# ATtiny.net
KiCad netlist of a schematic drawn in Altium Designer
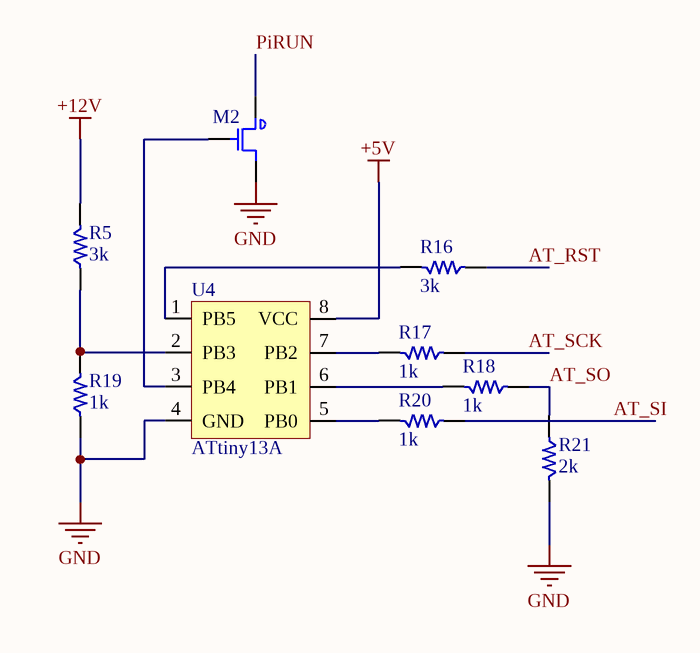
[diagram p0: ATtiny.SchDoc]

(export (version "E")
  (design (tool "Eeschema 10.0.6"))
  (components
    (comp (ref "M2")
      (value "N-CH Mosfet Switch")
      (footprint "SOT32-3")
      (description "MOSFET N-CH 20V 1.05A SOT23")
      (fields
        (field (name "MANUFACTURER") "NXP USA Inc.")
        (field (name "MANUFACTURER PART NUMBER") "BSH105,215")
      )
      (libsource (lib "SIM808") (part "BSH105,215"))
    )
    (comp (ref "R5")
      (value "3k")
      (footprint "0805")
      (description "Generic Resistor")
      (fields (field (name "Comment") "Resistor"))
      (libsource (lib "PowerCircuit") (part "Resistor"))
    )
    (comp (ref "R16")
      (value "3k")
      (footprint "0805")
      (description "Generic Resistor")
      (fields (field (name "Comment") "Resistor"))
      (libsource (lib "PowerCircuit") (part "Resistor"))
    )
    (comp (ref "R17")
      (value "1k")
      (footprint "0805")
      (description "Generic Resistor")
      (fields (field (name "Comment") "Resistor"))
      (libsource (lib "PowerCircuit") (part "Resistor"))
    )
    (comp (ref "R18")
      (value "1k")
      (footprint "0805")
      (description "Generic Resistor")
      (fields (field (name "Comment") "Resistor"))
      (libsource (lib "PowerCircuit") (part "Resistor"))
    )
    (comp (ref "R19")
      (value "1k")
      (footprint "0805")
      (description "Generic Resistor")
      (fields (field (name "Comment") "Resistor"))
      (libsource (lib "PowerCircuit") (part "Resistor"))
    )
    (comp (ref "R20")
      (value "1k")
      (footprint "0805")
      (description "Generic Resistor")
      (fields (field (name "Comment") "Resistor"))
      (libsource (lib "PowerCircuit") (part "Resistor"))
    )
    (comp (ref "R21")
      (value "2k")
      (footprint "0805")
      (description "Generic Resistor")
      (fields (field (name "Comment") "Resistor"))
      (libsource (lib "PowerCircuit") (part "Resistor"))
    )
    (comp (ref "U4")
      (value "ATtiny13A")
      (footprint "ATtiny13A")
      (fields
        (field (name "MANUFACTURER") "Microchip Technology")
        (field (name "MANUFACTURER PART NUMBER") "ATTINY13A-SSU")
      )
      (libsource (lib "ATtiny") (part "ATtiny13A"))
    )
  )
  (nets
    (net (code "1") (name "+5V") (class "Default")
      (node (ref "U4") (pin "8") (pinfunction "VCC_8") (pintype "passive"))
    )
    (net (code "2") (name "+12V") (class "Default")
      (node (ref "R5") (pin "2") (pinfunction "2_2") (pintype "passive"))
    )
    (net (code "3") (name "/AT_RST") (class "Default")
      (node (ref "R16") (pin "1") (pinfunction "1_1") (pintype "passive"))
    )
    (net (code "4") (name "/AT_SCK") (class "Default")
      (node (ref "R17") (pin "1") (pinfunction "1_1") (pintype "passive"))
    )
    (net (code "5") (name "/AT_SI") (class "Default")
      (node (ref "R20") (pin "1") (pinfunction "1_1") (pintype "passive"))
    )
    (net (code "6") (name "/AT_SO") (class "Default")
      (node (ref "R18") (pin "1") (pinfunction "1_1") (pintype "passive"))
      (node (ref "R21") (pin "1") (pinfunction "1_1") (pintype "passive"))
    )
    (net (code "7") (name "/PiRUN") (class "Default")
      (node (ref "M2") (pin "3") (pinfunction "D_3") (pintype "passive"))
    )
    (net (code "8") (name "GND") (class "Default")
      (node (ref "M2") (pin "2") (pinfunction "S_2") (pintype "passive"))
      (node (ref "R19") (pin "1") (pinfunction "1_1") (pintype "passive"))
      (node (ref "R21") (pin "2") (pinfunction "2_2") (pintype "passive"))
      (node (ref "U4") (pin "4") (pinfunction "GND_4") (pintype "passive"))
    )
    (net (code "9") (name "Net-(M2-G)") (class "Default")
      (node (ref "M2") (pin "1") (pinfunction "G_1") (pintype "passive"))
      (node (ref "U4") (pin "3") (pinfunction "PB4_3") (pintype "passive"))
    )
    (net (code "10") (name "Net-(U4-PB0)") (class "Default")
      (node (ref "R20") (pin "2") (pinfunction "2_2") (pintype "passive"))
      (node (ref "U4") (pin "5") (pinfunction "PB0_5") (pintype "passive"))
    )
    (net (code "11") (name "Net-(U4-PB1)") (class "Default")
      (node (ref "R18") (pin "2") (pinfunction "2_2") (pintype "passive"))
      (node (ref "U4") (pin "6") (pinfunction "PB1_6") (pintype "passive"))
    )
    (net (code "12") (name "Net-(U4-PB2)") (class "Default")
      (node (ref "R17") (pin "2") (pinfunction "2_2") (pintype "passive"))
      (node (ref "U4") (pin "7") (pinfunction "PB2_7") (pintype "passive"))
    )
    (net (code "13") (name "Net-(U4-PB3)") (class "Default")
      (node (ref "R19") (pin "2") (pinfunction "2_2") (pintype "passive"))
      (node (ref "R5") (pin "1") (pinfunction "1_1") (pintype "passive"))
      (node (ref "U4") (pin "2") (pinfunction "PB3_2") (pintype "passive"))
    )
    (net (code "14") (name "Net-(U4-PB5)") (class "Default")
      (node (ref "R16") (pin "2") (pinfunction "2_2") (pintype "passive"))
      (node (ref "U4") (pin "1") (pinfunction "PB5_1") (pintype "passive"))
    )
  )
)
